# 11_MSM8916_POWER2.net
KiCad netlist of a schematic drawn in Altium Designer
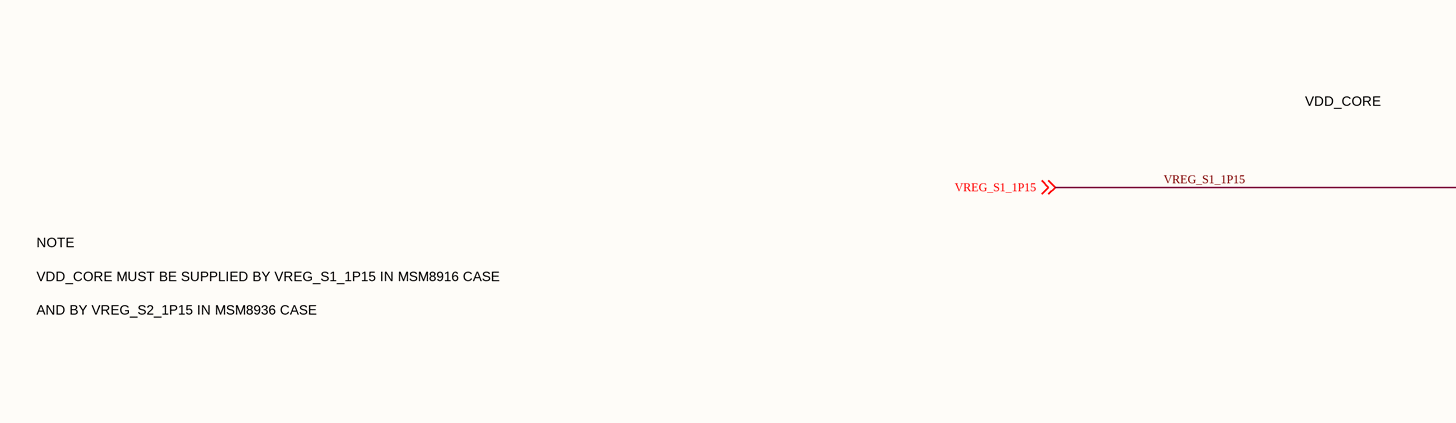
[diagram p0: 11 MSM8916_POWER2.SchDoc, top left]
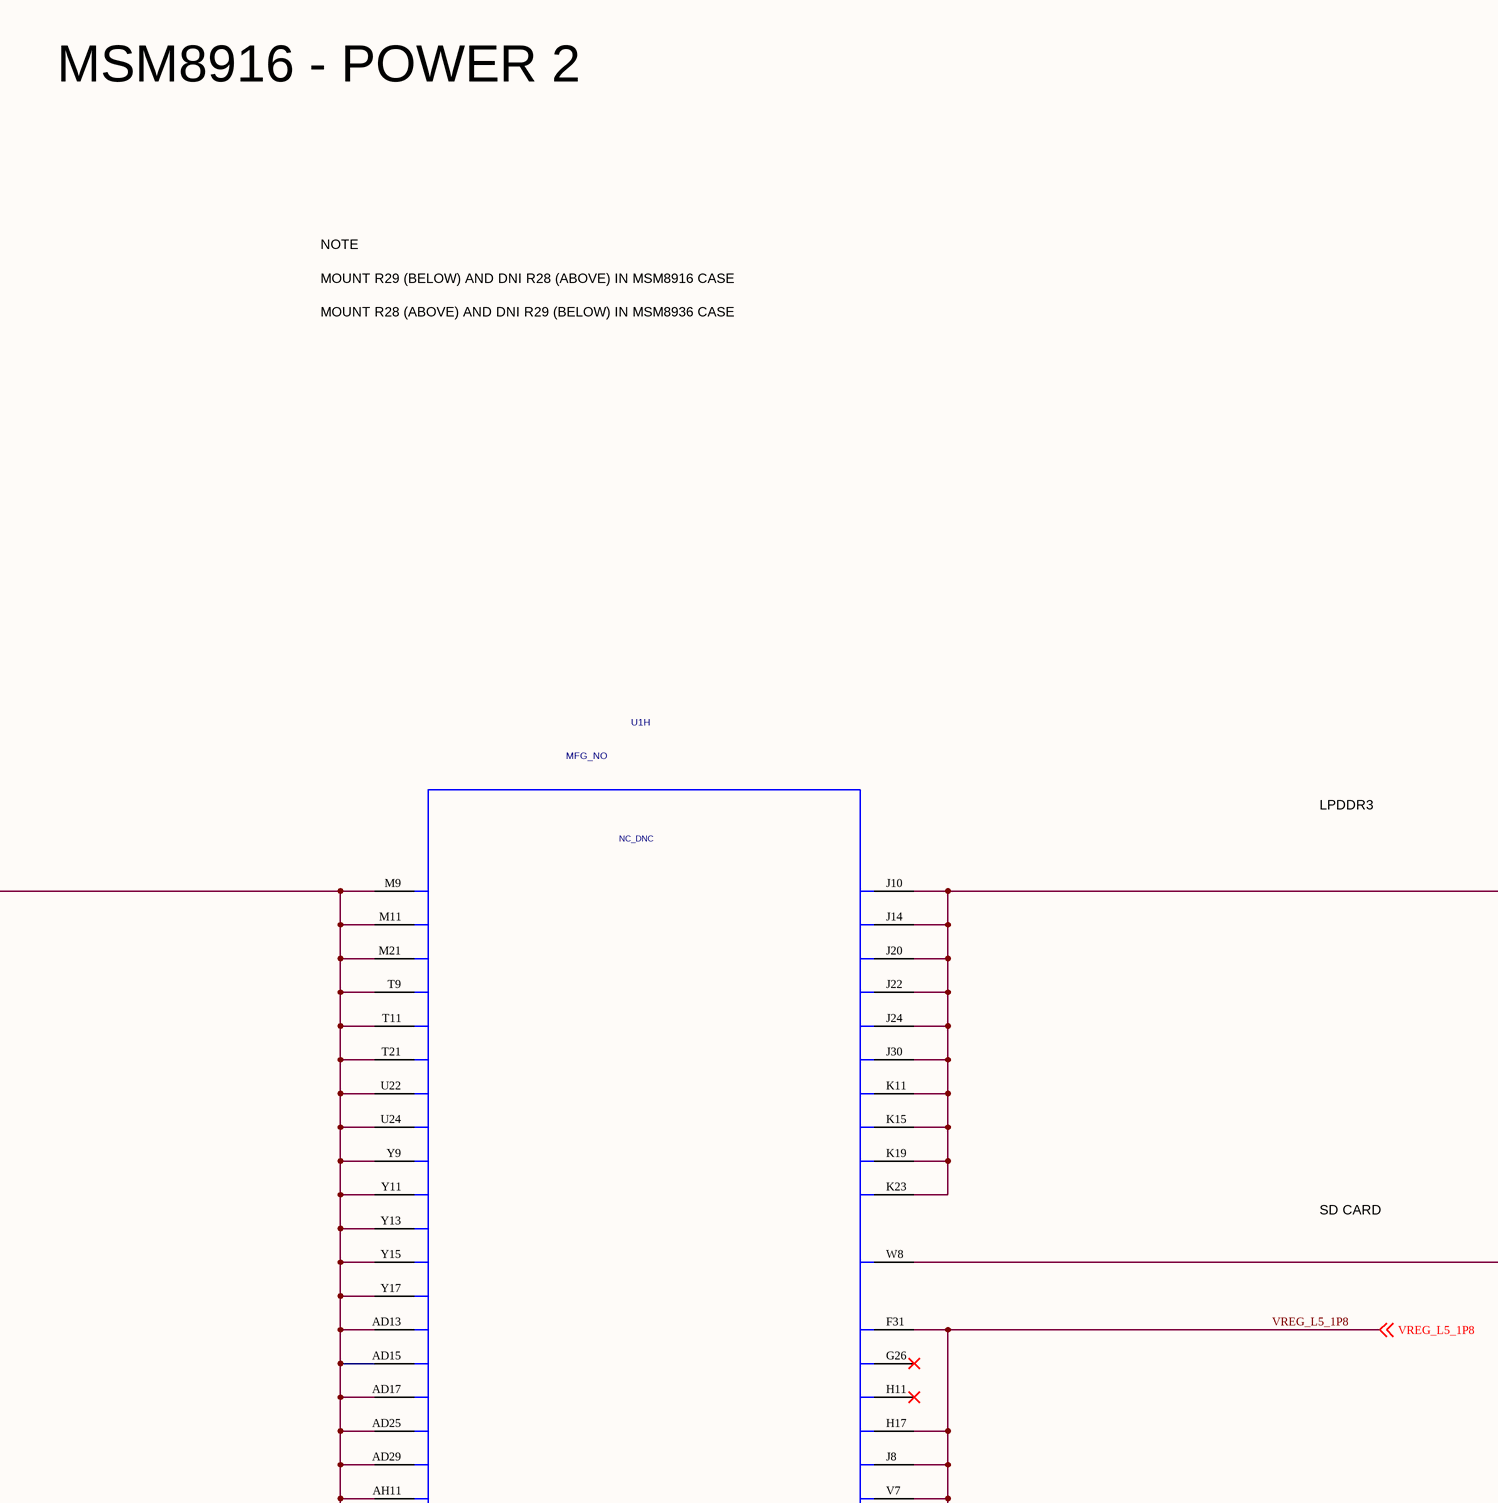
[diagram p1: 11 MSM8916_POWER2.SchDoc, top middle]
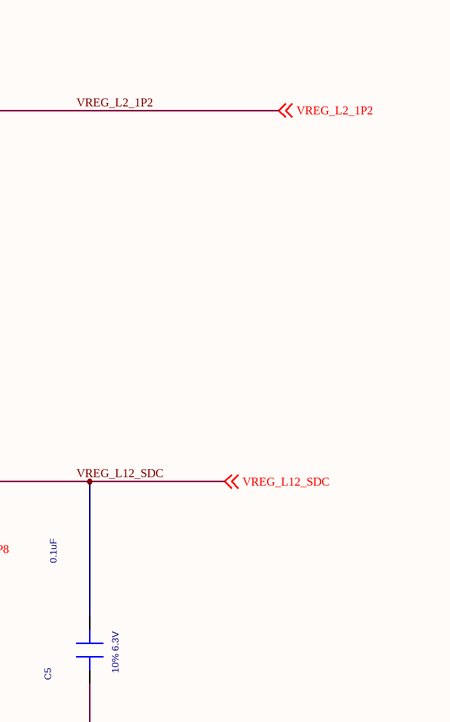
[diagram p2: 11 MSM8916_POWER2.SchDoc, top right]
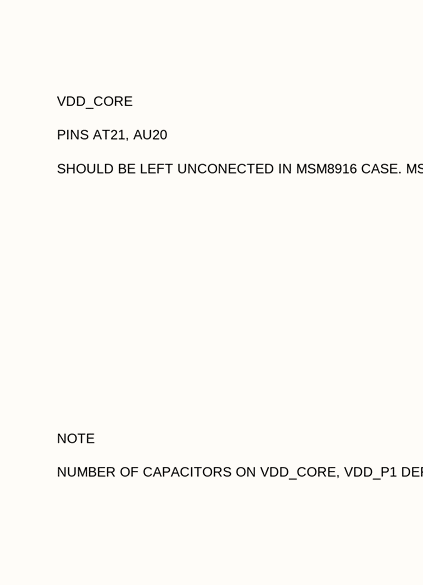
[diagram p3: 11 MSM8916_POWER2.SchDoc, bottom left]
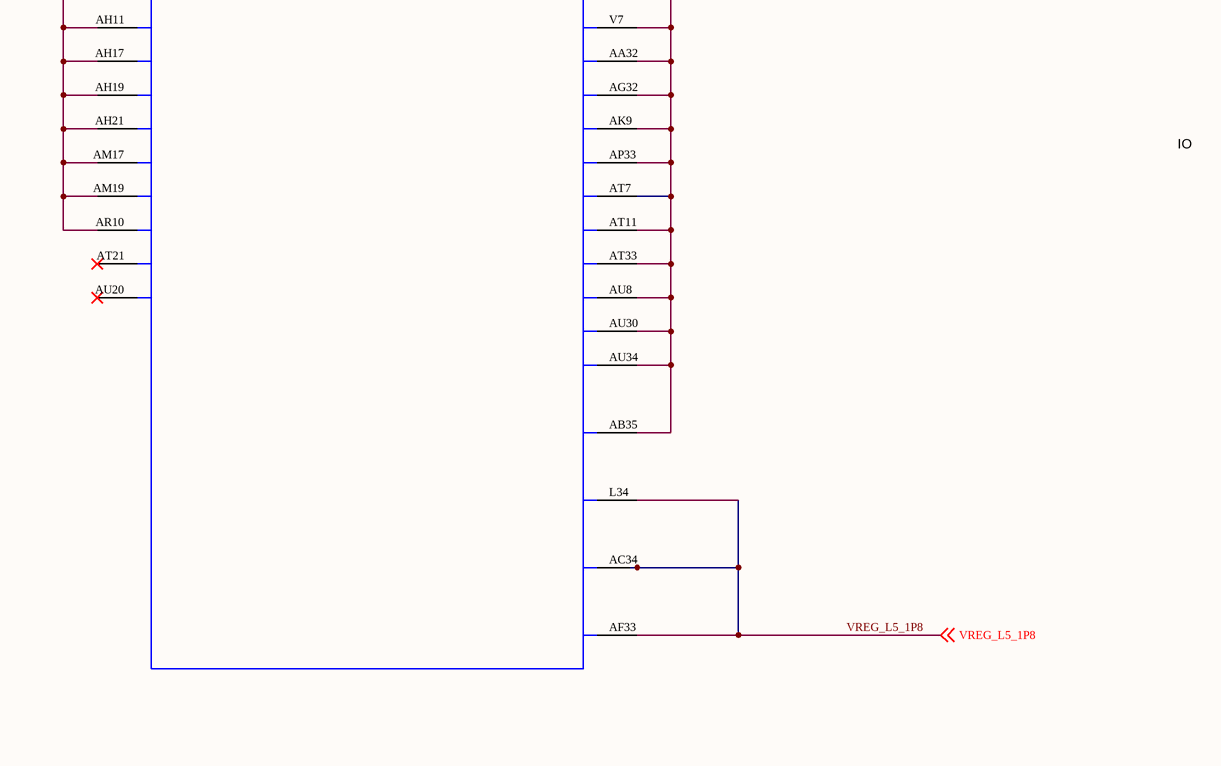
[diagram p4: 11 MSM8916_POWER2.SchDoc, bottom middle]
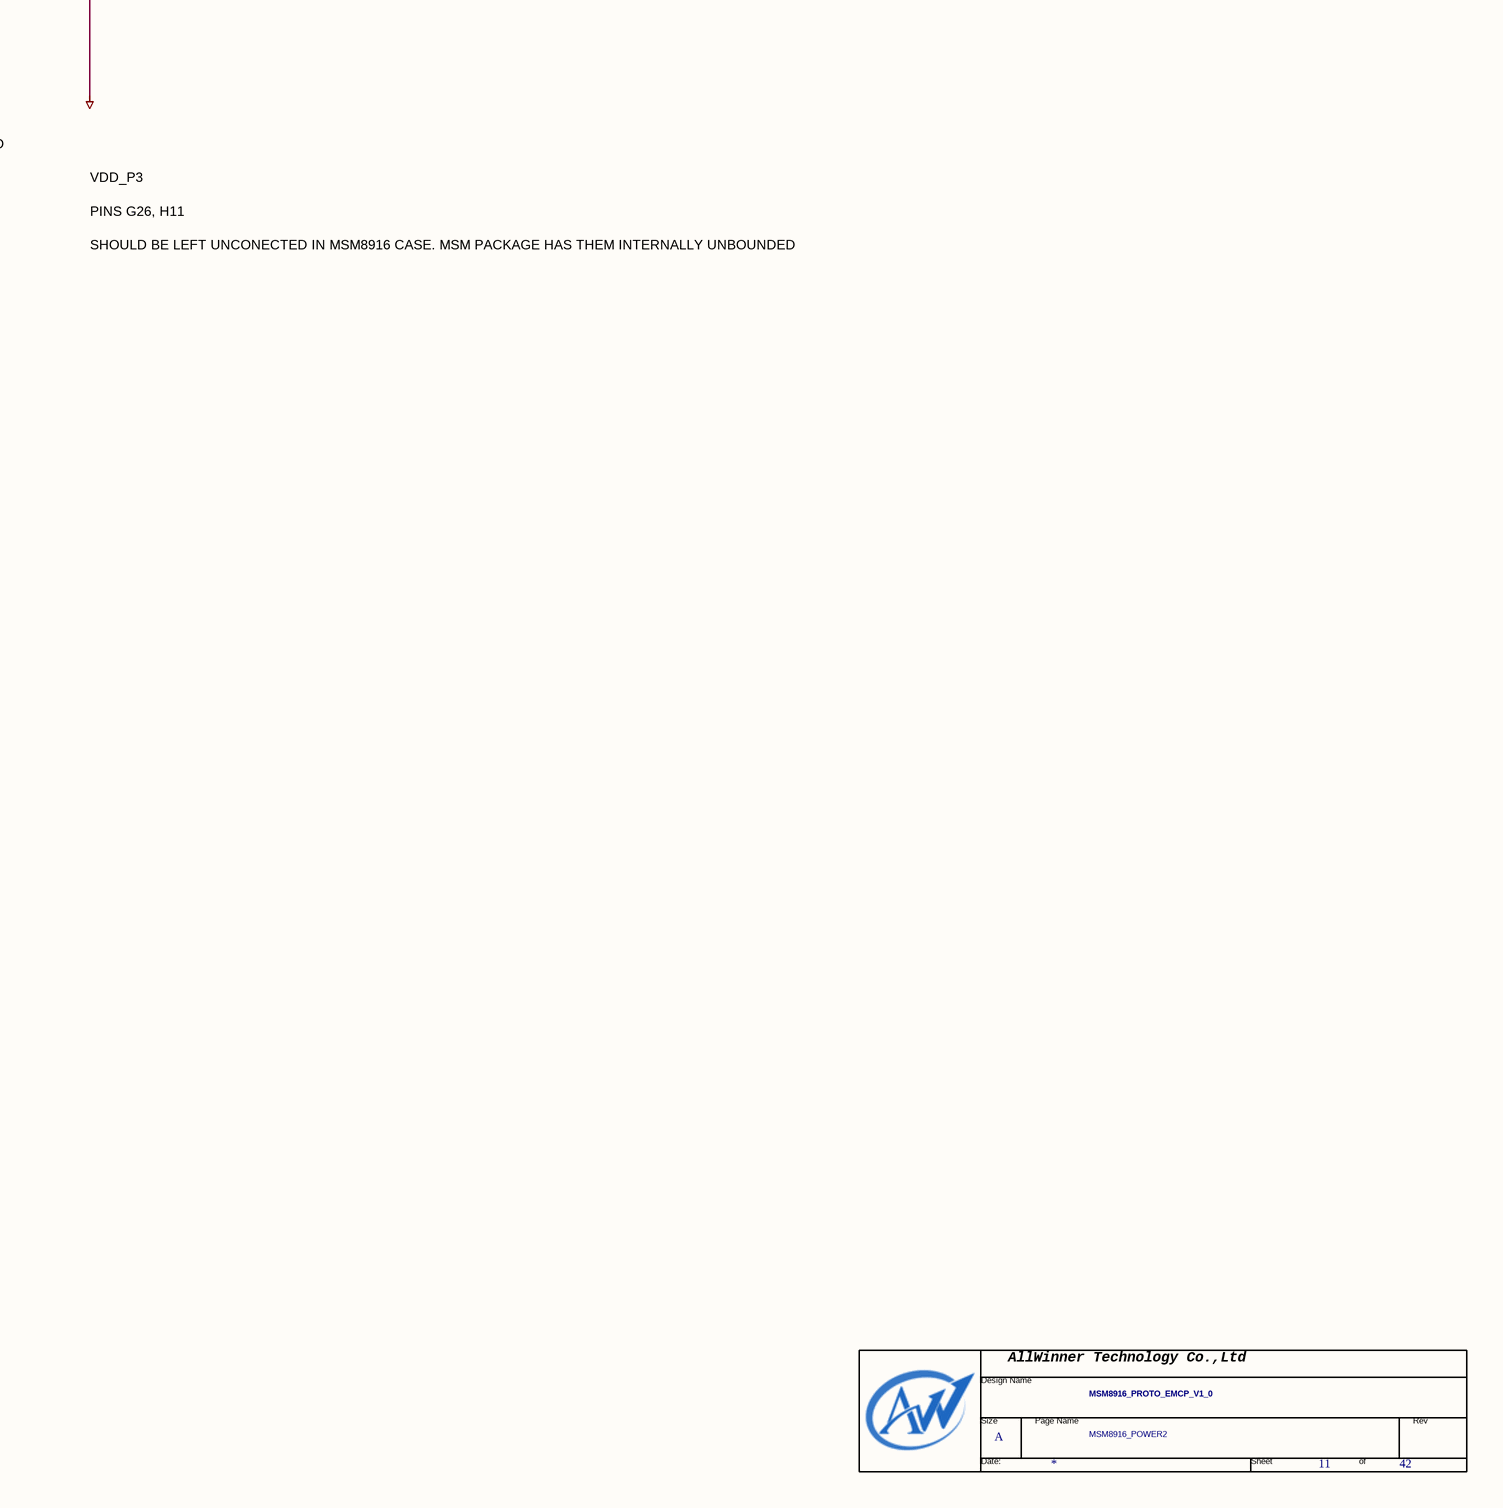
[diagram p5: 11 MSM8916_POWER2.SchDoc, bottom right]

(export (version "E")
  (design (tool "Eeschema 10.0.6"))
  (components
    (comp (ref "*")
      (value "TitleBlock0-AW")
      (fields
        (field (name "PAGE COUNT") "42")
        (field (name "PAGE NUMBER") "11")
        (field (name "PAGE SIZE") "A")
        (field (name "TITLE") "MSM8916_PROTO_EMCP_V1_0")
        (field (name "DOC") "MSM8916_POWER2")
      )
      (libsource (lib "*") (part "TitleBlock0-AW"))
    )
    (comp (ref "C5")
      (value "0.1uF")
      (fields (field (name "TOLERANCE") "10% 6.3V") (field (name "PART_NUMBER") "MCN_NO"))
      (libsource (lib "MSM8916_DRAM_PMIC_REF_Library") (part "CAP#1"))
    )
    (comp (ref "U1")
      (value "ASIC_MSM8936_760PIN")
      (footprint "MSM-8916-0-760NSP-TR-00-0")
      (fields
        (field (name "SYMNAME") "NC_DNC")
        (field (name "PART_NUMBER") "MCN_NO")
        (field (name "PART_ID") "MFG_NO")
      )
      (libsource (lib "MSM8916_DRAM_PMIC_REF_Library") (part "ASIC_MSM8936_760PIN"))
    )
  )
  (nets
    (net (code "1") (name "DGND") (class "Default")
      (node (ref "C5") (pin "1") (pinfunction "POS_1") (pintype "bidirectional"))
    )
    (net (code "2") (name "VREG_L2_1P2") (class "Default")
      (node (ref "U1") (pin "J10") (pinfunction "VDDPX_1_1_J10") (pintype "power_in"))
      (node (ref "U1") (pin "J14") (pinfunction "VDDPX_1_2_J14") (pintype "power_in"))
      (node (ref "U1") (pin "J20") (pinfunction "VDDPX_1_3_J20") (pintype "power_in"))
      (node (ref "U1") (pin "J22") (pinfunction "VDDPX_1_4_J22") (pintype "power_in"))
      (node (ref "U1") (pin "J24") (pinfunction "VDDPX_1_5_J24") (pintype "power_in"))
      (node (ref "U1") (pin "J30") (pinfunction "VDDPX_1_6_J30") (pintype "power_in"))
      (node (ref "U1") (pin "K11") (pinfunction "VDDPX_1_7_K11") (pintype "power_in"))
      (node (ref "U1") (pin "K15") (pinfunction "VDDPX_1_8_K15") (pintype "power_in"))
      (node (ref "U1") (pin "K19") (pinfunction "VDDPX_1_9_K19") (pintype "power_in"))
      (node (ref "U1") (pin "K23") (pinfunction "VDDPX_1_10_K23") (pintype "power_in"))
    )
    (net (code "3") (name "VREG_L5_1P8") (class "Default")
      (node (ref "U1") (pin "AA32") (pinfunction "VDDPX_3_7_AA32") (pintype "power_in"))
      (node (ref "U1") (pin "AB35") (pinfunction "VDDPX_4_AB35") (pintype "power_in"))
      (node (ref "U1") (pin "AC34") (pinfunction "VDDPX_6_AC34") (pintype "power_in"))
      (node (ref "U1") (pin "AF33") (pinfunction "VDDPX_7_AF33") (pintype "power_in"))
      (node (ref "U1") (pin "AG32") (pinfunction "VDDPX_3_8_AG32") (pintype "power_in"))
      (node (ref "U1") (pin "AK9") (pinfunction "VDDPX_3_9_AK9") (pintype "power_in"))
      (node (ref "U1") (pin "AP33") (pinfunction "VDDPX_3_10_AP33") (pintype "power_in"))
      (node (ref "U1") (pin "AT11") (pinfunction "VDDPX_3_12_AT11") (pintype "power_in"))
      (node (ref "U1") (pin "AT33") (pinfunction "VDDPX_3_13_AT33") (pintype "power_in"))
      (node (ref "U1") (pin "AT7") (pinfunction "VDDPX_3_11_AT7") (pintype "power_in"))
      (node (ref "U1") (pin "AU30") (pinfunction "VDDPX_3_15_AU30") (pintype "power_in"))
      (node (ref "U1") (pin "AU34") (pinfunction "VDDPX_3_16_AU34") (pintype "power_in"))
      (node (ref "U1") (pin "AU8") (pinfunction "VDDPX_3_14_AU8") (pintype "power_in"))
      (node (ref "U1") (pin "F31") (pinfunction "VDDPX_3_1_F31") (pintype "power_in"))
      (node (ref "U1") (pin "H17") (pinfunction "VDDPX_3_4_H17") (pintype "power_in"))
      (node (ref "U1") (pin "J8") (pinfunction "VDDPX_3_5_J8") (pintype "power_in"))
      (node (ref "U1") (pin "L34") (pinfunction "VDDPX_5_L34") (pintype "power_in"))
      (node (ref "U1") (pin "V7") (pinfunction "VDDPX_3_6_V7") (pintype "power_in"))
    )
    (net (code "4") (name "VREG_L12_SDC") (class "Default")
      (node (ref "C5") (pin "2") (pinfunction "NEG_2") (pintype "bidirectional"))
      (node (ref "U1") (pin "W8") (pinfunction "VDDPX_2_W8") (pintype "power_in"))
    )
    (net (code "5") (name "VREG_S1_1P15") (class "Default")
      (node (ref "U1") (pin "AD13") (pinfunction "VDDCX_1_14_AD13") (pintype "power_in"))
      (node (ref "U1") (pin "AD15") (pinfunction "VDDCX_1_15_AD15") (pintype "power_in"))
      (node (ref "U1") (pin "AD17") (pinfunction "VDDCX_1_16_AD17") (pintype "power_in"))
      (node (ref "U1") (pin "AD25") (pinfunction "VDDCX_1_17_AD25") (pintype "power_in"))
      (node (ref "U1") (pin "AD29") (pinfunction "VDDCX_1_18_AD29") (pintype "power_in"))
      (node (ref "U1") (pin "AH11") (pinfunction "VDDCX_1_19_AH11") (pintype "power_in"))
      (node (ref "U1") (pin "AH17") (pinfunction "VDDCX_1_20_AH17") (pintype "power_in"))
      (node (ref "U1") (pin "AH19") (pinfunction "VDDCX_1_21_AH19") (pintype "power_in"))
      (node (ref "U1") (pin "AH21") (pinfunction "VDDCX_1_22_AH21") (pintype "power_in"))
      (node (ref "U1") (pin "AM17") (pinfunction "VDDCX_1_23_AM17") (pintype "power_in"))
      (node (ref "U1") (pin "AM19") (pinfunction "VDDCX_1_24_AM19") (pintype "power_in"))
      (node (ref "U1") (pin "AR10") (pinfunction "VDDCX_1_25_AR10") (pintype "power_in"))
      (node (ref "U1") (pin "M11") (pinfunction "VDDCX_1_2_M11") (pintype "power_in"))
      (node (ref "U1") (pin "M21") (pinfunction "VDDCX_1_3_M21") (pintype "power_in"))
      (node (ref "U1") (pin "M9") (pinfunction "VDDCX_1_1_M9") (pintype "power_in"))
      (node (ref "U1") (pin "T11") (pinfunction "VDDCX_1_5_T11") (pintype "power_in"))
      (node (ref "U1") (pin "T21") (pinfunction "VDDCX_1_6_T21") (pintype "power_in"))
      (node (ref "U1") (pin "T9") (pinfunction "VDDCX_1_4_T9") (pintype "power_in"))
      (node (ref "U1") (pin "U22") (pinfunction "VDDCX_1_7_U22") (pintype "power_in"))
      (node (ref "U1") (pin "U24") (pinfunction "VDDCX_1_8_U24") (pintype "power_in"))
      (node (ref "U1") (pin "Y11") (pinfunction "VDDCX_1_10_Y11") (pintype "power_in"))
      (node (ref "U1") (pin "Y13") (pinfunction "VDDCX_1_11_Y13") (pintype "power_in"))
      (node (ref "U1") (pin "Y15") (pinfunction "VDDCX_1_12_Y15") (pintype "power_in"))
      (node (ref "U1") (pin "Y17") (pinfunction "VDDCX_1_13_Y17") (pintype "power_in"))
      (node (ref "U1") (pin "Y9") (pinfunction "VDDCX_1_9_Y9") (pintype "power_in"))
    )
    (net (code "6") (name "unconnected-(U1H-VDDCX_1_26-PadAT21)") (class "Default")
      (node (ref "U1") (pin "AT21") (pinfunction "VDDCX_1_26_AT21") (pintype "power_in+no_connect"))
    )
    (net (code "7") (name "unconnected-(U1H-VDDCX_1_27-PadAU20)") (class "Default")
      (node (ref "U1") (pin "AU20") (pinfunction "VDDCX_1_27_AU20") (pintype "power_in+no_connect"))
    )
    (net (code "8") (name "unconnected-(U1H-VDDPX_3_2-PadG26)") (class "Default")
      (node (ref "U1") (pin "G26") (pinfunction "VDDPX_3_2_G26") (pintype "power_in+no_connect"))
    )
    (net (code "9") (name "unconnected-(U1H-VDDPX_3_3-PadH11)") (class "Default")
      (node (ref "U1") (pin "H11") (pinfunction "VDDPX_3_3_H11") (pintype "power_in+no_connect"))
    )
  )
)
